# Relay.net
KiCad netlist of a schematic drawn in Altium Designer
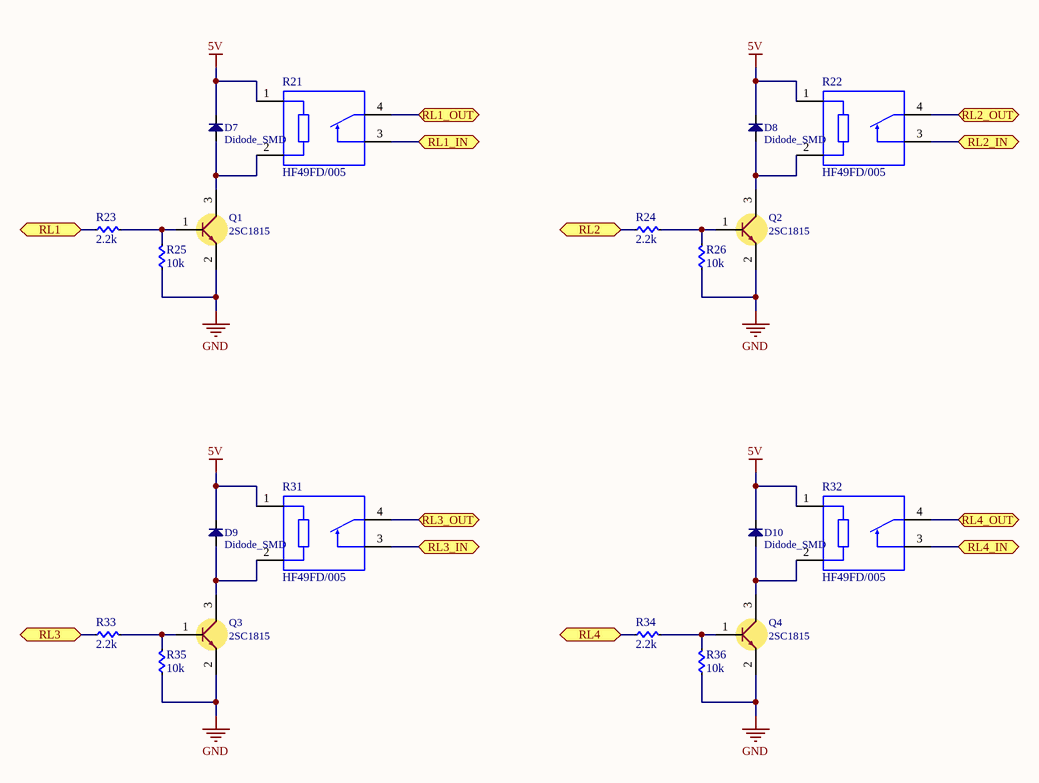
[diagram p0: Relay.SchDoc]

(export (version "E")
  (design (tool "Eeschema 10.0.6"))
  (components
    (comp (ref "D7")
      (value "Didode_SMD")
      (footprint "SOD-123")
      (fields (field (name "PUBLISHER") "Altium Limited"))
      (libsource (lib "Altium_Lib_PTK") (part "Didode_SMD"))
    )
    (comp (ref "D8")
      (value "Didode_SMD")
      (footprint "SOD-123")
      (fields (field (name "PUBLISHER") "Altium Limited"))
      (libsource (lib "Altium_Lib_PTK") (part "Didode_SMD"))
    )
    (comp (ref "D9")
      (value "Didode_SMD")
      (footprint "SOD-123")
      (fields (field (name "PUBLISHER") "Altium Limited"))
      (libsource (lib "Altium_Lib_PTK") (part "Didode_SMD"))
    )
    (comp (ref "D10")
      (value "Didode_SMD")
      (footprint "SOD-123")
      (fields (field (name "PUBLISHER") "Altium Limited"))
      (libsource (lib "Altium_Lib_PTK") (part "Didode_SMD"))
    )
    (comp (ref "Q1")
      (value "2SC1815")
      (footprint "SOT23")
      (description "SMD TRANSISTOR")
      (libsource (lib "VPMyLibrary") (part "NPN_SMD"))
    )
    (comp (ref "Q2")
      (value "2SC1815")
      (footprint "SOT23")
      (description "SMD TRANSISTOR")
      (libsource (lib "VPMyLibrary") (part "NPN_SMD"))
    )
    (comp (ref "Q3")
      (value "2SC1815")
      (footprint "SOT23")
      (description "SMD TRANSISTOR")
      (libsource (lib "VPMyLibrary") (part "NPN_SMD"))
    )
    (comp (ref "Q4")
      (value "2SC1815")
      (footprint "SOT23")
      (description "SMD TRANSISTOR")
      (libsource (lib "VPMyLibrary") (part "NPN_SMD"))
    )
    (comp (ref "R21")
      (value "HF49FD/005")
      (footprint "RELAY_HF49FD/005-1H12T")
      (description "Relay: electromagnetic; SPST-NO; Ucoil: 5VDC; 5A/250VAC; 5A/30VDC")
      (libsource (lib "Power PLC") (part "Relay HF49FD"))
    )
    (comp (ref "R22")
      (value "HF49FD/005")
      (footprint "RELAY_HF49FD/005-1H12T")
      (description "Relay: electromagnetic; SPST-NO; Ucoil: 5VDC; 5A/250VAC; 5A/30VDC")
      (libsource (lib "Power PLC") (part "Relay HF49FD"))
    )
    (comp (ref "R23")
      (value "2.2k")
      (footprint "RES 0603")
      (description "RES SMD 0603")
      (fields
        (field (name "MANUFACTURER") "Vishay Dale")
        (field (name "MANUFACTURER PART NUMBER") "CRCW040210K0FKED")
      )
      (libsource (lib "Altium_Lib_PTK") (part "RES 0603"))
    )
    (comp (ref "R24")
      (value "2.2k")
      (footprint "RES 0603")
      (description "RES SMD 0603")
      (fields
        (field (name "MANUFACTURER") "Vishay Dale")
        (field (name "MANUFACTURER PART NUMBER") "CRCW040210K0FKED")
      )
      (libsource (lib "Altium_Lib_PTK") (part "RES 0603"))
    )
    (comp (ref "R25")
      (value "10k")
      (footprint "RES 0603")
      (description "RES SMD 0603")
      (fields
        (field (name "MANUFACTURER") "Vishay Dale")
        (field (name "MANUFACTURER PART NUMBER") "CRCW040210K0FKED")
      )
      (libsource (lib "Altium_Lib_PTK") (part "RES 0603"))
    )
    (comp (ref "R26")
      (value "10k")
      (footprint "RES 0603")
      (description "RES SMD 0603")
      (fields
        (field (name "MANUFACTURER") "Vishay Dale")
        (field (name "MANUFACTURER PART NUMBER") "CRCW040210K0FKED")
      )
      (libsource (lib "Altium_Lib_PTK") (part "RES 0603"))
    )
    (comp (ref "R31")
      (value "HF49FD/005")
      (footprint "RELAY_HF49FD/005-1H12T")
      (description "Relay: electromagnetic; SPST-NO; Ucoil: 5VDC; 5A/250VAC; 5A/30VDC")
      (libsource (lib "Power PLC") (part "Relay HF49FD"))
    )
    (comp (ref "R32")
      (value "HF49FD/005")
      (footprint "RELAY_HF49FD/005-1H12T")
      (description "Relay: electromagnetic; SPST-NO; Ucoil: 5VDC; 5A/250VAC; 5A/30VDC")
      (libsource (lib "Power PLC") (part "Relay HF49FD"))
    )
    (comp (ref "R33")
      (value "2.2k")
      (footprint "RES 0603")
      (description "RES SMD 0603")
      (fields
        (field (name "MANUFACTURER") "Vishay Dale")
        (field (name "MANUFACTURER PART NUMBER") "CRCW040210K0FKED")
      )
      (libsource (lib "Altium_Lib_PTK") (part "RES 0603"))
    )
    (comp (ref "R34")
      (value "2.2k")
      (footprint "RES 0603")
      (description "RES SMD 0603")
      (fields
        (field (name "MANUFACTURER") "Vishay Dale")
        (field (name "MANUFACTURER PART NUMBER") "CRCW040210K0FKED")
      )
      (libsource (lib "Altium_Lib_PTK") (part "RES 0603"))
    )
    (comp (ref "R35")
      (value "10k")
      (footprint "RES 0603")
      (description "RES SMD 0603")
      (fields
        (field (name "MANUFACTURER") "Vishay Dale")
        (field (name "MANUFACTURER PART NUMBER") "CRCW040210K0FKED")
      )
      (libsource (lib "Altium_Lib_PTK") (part "RES 0603"))
    )
    (comp (ref "R36")
      (value "10k")
      (footprint "RES 0603")
      (description "RES SMD 0603")
      (fields
        (field (name "MANUFACTURER") "Vishay Dale")
        (field (name "MANUFACTURER PART NUMBER") "CRCW040210K0FKED")
      )
      (libsource (lib "Altium_Lib_PTK") (part "RES 0603"))
    )
  )
  (nets
    (net (code "1") (name "/RL1") (class "Default")
      (node (ref "R23") (pin "1") (pinfunction "1_1") (pintype "passive"))
    )
    (net (code "2") (name "/RL1_IN") (class "Default")
      (node (ref "R21") (pin "3") (pinfunction "C2_3") (pintype "passive"))
    )
    (net (code "3") (name "/RL1_OUT") (class "Default")
      (node (ref "R21") (pin "4") (pinfunction "C1_4") (pintype "passive"))
    )
    (net (code "4") (name "/RL2") (class "Default")
      (node (ref "R24") (pin "1") (pinfunction "1_1") (pintype "passive"))
    )
    (net (code "5") (name "/RL2_IN") (class "Default")
      (node (ref "R22") (pin "3") (pinfunction "C2_3") (pintype "passive"))
    )
    (net (code "6") (name "/RL2_OUT") (class "Default")
      (node (ref "R22") (pin "4") (pinfunction "C1_4") (pintype "passive"))
    )
    (net (code "7") (name "/RL3") (class "Default")
      (node (ref "R33") (pin "1") (pinfunction "1_1") (pintype "passive"))
    )
    (net (code "8") (name "/RL3_IN") (class "Default")
      (node (ref "R31") (pin "3") (pinfunction "C2_3") (pintype "passive"))
    )
    (net (code "9") (name "/RL3_OUT") (class "Default")
      (node (ref "R31") (pin "4") (pinfunction "C1_4") (pintype "passive"))
    )
    (net (code "10") (name "/RL4") (class "Default")
      (node (ref "R34") (pin "1") (pinfunction "1_1") (pintype "passive"))
    )
    (net (code "11") (name "/RL4_IN") (class "Default")
      (node (ref "R32") (pin "3") (pinfunction "C2_3") (pintype "passive"))
    )
    (net (code "12") (name "/RL4_OUT") (class "Default")
      (node (ref "R32") (pin "4") (pinfunction "C1_4") (pintype "passive"))
    )
    (net (code "13") (name "5V") (class "Default")
      (node (ref "D10") (pin "2") (pinfunction "K_2") (pintype "passive"))
      (node (ref "D7") (pin "2") (pinfunction "K_2") (pintype "passive"))
      (node (ref "D8") (pin "2") (pinfunction "K_2") (pintype "passive"))
      (node (ref "D9") (pin "2") (pinfunction "K_2") (pintype "passive"))
      (node (ref "R21") (pin "1") (pinfunction "L1_1") (pintype "passive"))
      (node (ref "R22") (pin "1") (pinfunction "L1_1") (pintype "passive"))
      (node (ref "R31") (pin "1") (pinfunction "L1_1") (pintype "passive"))
      (node (ref "R32") (pin "1") (pinfunction "L1_1") (pintype "passive"))
    )
    (net (code "14") (name "GND") (class "Default")
      (node (ref "Q1") (pin "2") (pinfunction "E_2") (pintype "passive"))
      (node (ref "Q2") (pin "2") (pinfunction "E_2") (pintype "passive"))
      (node (ref "Q3") (pin "2") (pinfunction "E_2") (pintype "passive"))
      (node (ref "Q4") (pin "2") (pinfunction "E_2") (pintype "passive"))
      (node (ref "R25") (pin "1") (pinfunction "1_1") (pintype "passive"))
      (node (ref "R26") (pin "1") (pinfunction "1_1") (pintype "passive"))
      (node (ref "R35") (pin "1") (pinfunction "1_1") (pintype "passive"))
      (node (ref "R36") (pin "1") (pinfunction "1_1") (pintype "passive"))
    )
    (net (code "15") (name "Net-(D7-A)") (class "Default")
      (node (ref "D7") (pin "1") (pinfunction "A_1") (pintype "passive"))
      (node (ref "Q1") (pin "3") (pinfunction "C_3") (pintype "passive"))
      (node (ref "R21") (pin "2") (pinfunction "L2_2") (pintype "passive"))
    )
    (net (code "16") (name "Net-(D8-A)") (class "Default")
      (node (ref "D8") (pin "1") (pinfunction "A_1") (pintype "passive"))
      (node (ref "Q2") (pin "3") (pinfunction "C_3") (pintype "passive"))
      (node (ref "R22") (pin "2") (pinfunction "L2_2") (pintype "passive"))
    )
    (net (code "17") (name "Net-(D9-A)") (class "Default")
      (node (ref "D9") (pin "1") (pinfunction "A_1") (pintype "passive"))
      (node (ref "Q3") (pin "3") (pinfunction "C_3") (pintype "passive"))
      (node (ref "R31") (pin "2") (pinfunction "L2_2") (pintype "passive"))
    )
    (net (code "18") (name "Net-(D10-A)") (class "Default")
      (node (ref "D10") (pin "1") (pinfunction "A_1") (pintype "passive"))
      (node (ref "Q4") (pin "3") (pinfunction "C_3") (pintype "passive"))
      (node (ref "R32") (pin "2") (pinfunction "L2_2") (pintype "passive"))
    )
    (net (code "19") (name "Net-(Q1-B)") (class "Default")
      (node (ref "Q1") (pin "1") (pinfunction "B_1") (pintype "passive"))
      (node (ref "R23") (pin "2") (pinfunction "2_2") (pintype "passive"))
      (node (ref "R25") (pin "2") (pinfunction "2_2") (pintype "passive"))
    )
    (net (code "20") (name "Net-(Q2-B)") (class "Default")
      (node (ref "Q2") (pin "1") (pinfunction "B_1") (pintype "passive"))
      (node (ref "R24") (pin "2") (pinfunction "2_2") (pintype "passive"))
      (node (ref "R26") (pin "2") (pinfunction "2_2") (pintype "passive"))
    )
    (net (code "21") (name "Net-(Q3-B)") (class "Default")
      (node (ref "Q3") (pin "1") (pinfunction "B_1") (pintype "passive"))
      (node (ref "R33") (pin "2") (pinfunction "2_2") (pintype "passive"))
      (node (ref "R35") (pin "2") (pinfunction "2_2") (pintype "passive"))
    )
    (net (code "22") (name "Net-(Q4-B)") (class "Default")
      (node (ref "Q4") (pin "1") (pinfunction "B_1") (pintype "passive"))
      (node (ref "R34") (pin "2") (pinfunction "2_2") (pintype "passive"))
      (node (ref "R36") (pin "2") (pinfunction "2_2") (pintype "passive"))
    )
  )
)
